# rpi-receiver.net
KiCad netlist of a schematic drawn in EAGLE
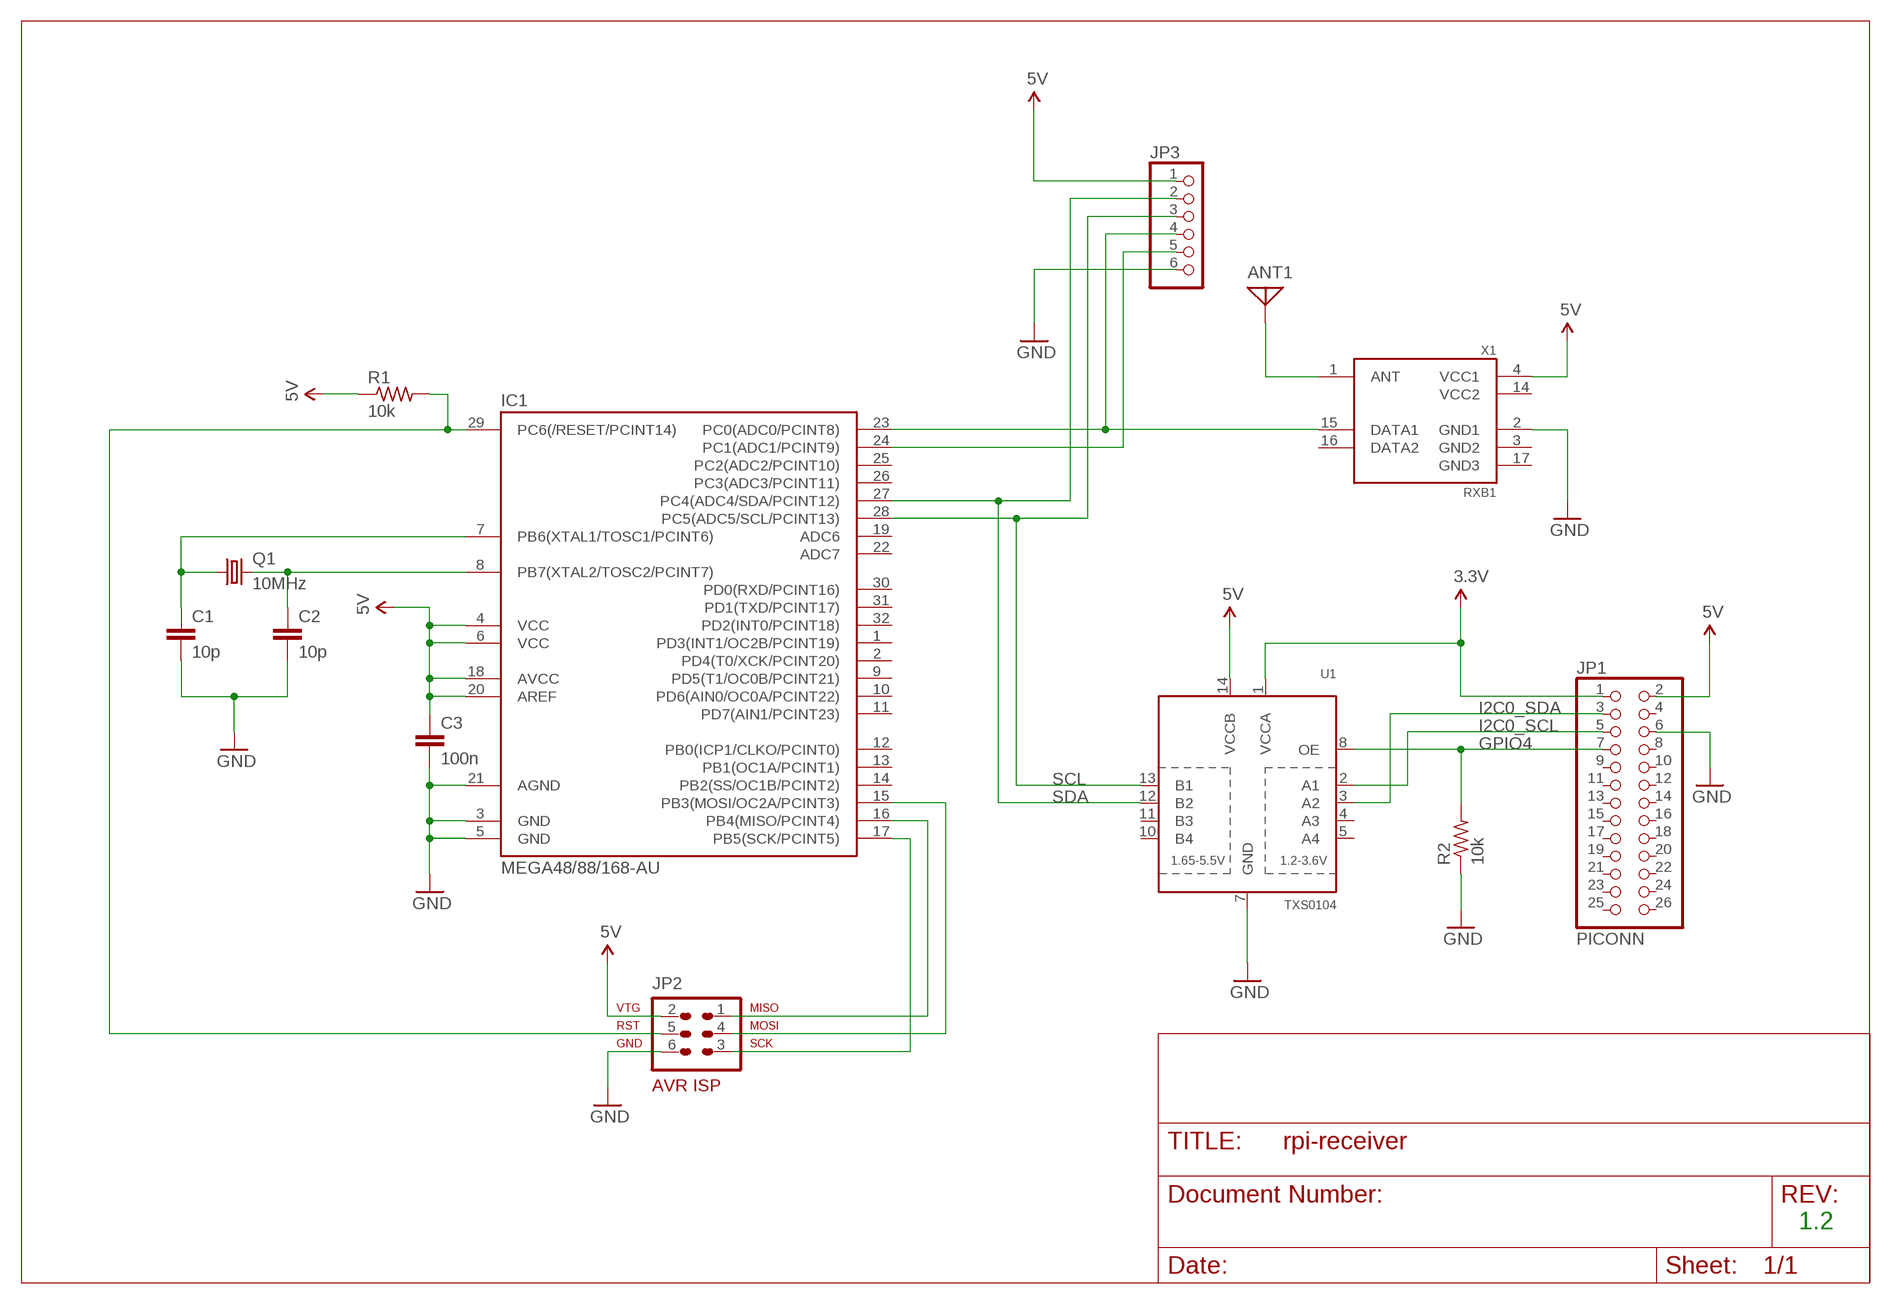
[diagram p0: schematic, sheet 1]

(export (version "E")
  (design (tool "Eeschema 10.0.6"))
  (components
    (comp (ref "ANT1")
      (value "ANTENNA")
      (footprint "eagle-import:PAD-01")
      (libsource (lib "eagle-import") (part "ANTENNA"))
    )
    (comp (ref "C1")
      (value "10p")
      (footprint "eagle-import:C0805")
      (libsource (lib "eagle-import") (part "C-EUC0805"))
    )
    (comp (ref "C2")
      (value "10p")
      (footprint "eagle-import:C0805")
      (libsource (lib "eagle-import") (part "C-EUC0805"))
    )
    (comp (ref "C3")
      (value "100n")
      (footprint "eagle-import:C0805")
      (libsource (lib "eagle-import") (part "C-EUC0805"))
    )
    (comp (ref "IC1")
      (value "MEGA48/88/168-AU")
      (footprint "eagle-import:TQFP32-08")
      (libsource (lib "eagle-import") (part "MEGA48/88/168-AU"))
    )
    (comp (ref "JP1")
      (value "PICONN")
      (footprint "eagle-import:2X13")
      (libsource (lib "eagle-import") (part "PINHD-2X13"))
    )
    (comp (ref "JP2")
      (value "AVR-ISP-6POL-HDR")
      (footprint "eagle-import:22-23-2061")
      (libsource (lib "eagle-import") (part "AVR-ISP-6POL-HDR"))
    )
    (comp (ref "JP3")
      (value "PINHD-1X6")
      (footprint "eagle-import:1X06")
      (libsource (lib "eagle-import") (part "PINHD-1X6"))
    )
    (comp (ref "Q1")
      (value "10MHz")
      (footprint "eagle-import:HC49UP")
      (libsource (lib "eagle-import") (part "CRYSTALHC49UP"))
    )
    (comp (ref "R1")
      (value "10k")
      (footprint "eagle-import:M0805")
      (libsource (lib "eagle-import") (part "R-US_M0805"))
    )
    (comp (ref "R2")
      (value "10k")
      (footprint "eagle-import:M0805")
      (libsource (lib "eagle-import") (part "R-US_M0805"))
    )
    (comp (ref "U1")
      (value "TXS0104")
      (footprint "eagle-import:TSSOP14")
      (libsource (lib "eagle-import") (part "TXB0104PWR"))
    )
    (comp (ref "X1")
      (value "RXB1")
      (footprint "eagle-import:RXB1")
      (libsource (lib "eagle-import") (part "RXB1"))
    )
  )
  (nets
    (net (code "1") (name "/GND2") (class "Default")
      (node (ref "X1") (pin "3") (pinfunction "GND2_3") (pintype "power_in"))
    )
    (net (code "2") (name "/GND3") (class "Default")
      (node (ref "X1") (pin "17") (pinfunction "GND3_17") (pintype "power_in"))
    )
    (net (code "3") (name "/GPIO4") (class "Default")
      (node (ref "JP1") (pin "7") (pinfunction "7_7") (pintype "passive"))
      (node (ref "R2") (pin "2") (pinfunction "2_2") (pintype "passive"))
      (node (ref "U1") (pin "8") (pinfunction "OE_8") (pintype "bidirectional"))
    )
    (net (code "4") (name "/I2C0_SCL") (class "Default")
      (node (ref "JP1") (pin "5") (pinfunction "5_5") (pintype "passive"))
      (node (ref "U1") (pin "2") (pinfunction "A1_2") (pintype "bidirectional"))
    )
    (net (code "5") (name "/I2C0_SDA") (class "Default")
      (node (ref "JP1") (pin "3") (pinfunction "3_3") (pintype "passive"))
      (node (ref "U1") (pin "3") (pinfunction "A2_3") (pintype "bidirectional"))
    )
    (net (code "6") (name "/SCL") (class "Default")
      (node (ref "IC1") (pin "28") (pinfunction "PC5(ADC5/SCL/PCINT13)_28") (pintype "bidirectional"))
      (node (ref "JP3") (pin "3") (pinfunction "3_3") (pintype "passive"))
      (node (ref "U1") (pin "13") (pinfunction "B1_13") (pintype "bidirectional"))
    )
    (net (code "7") (name "/SDA") (class "Default")
      (node (ref "IC1") (pin "27") (pinfunction "PC4(ADC4/SDA/PCINT12)_27") (pintype "bidirectional"))
      (node (ref "JP3") (pin "2") (pinfunction "2_2") (pintype "passive"))
      (node (ref "U1") (pin "12") (pinfunction "B2_12") (pintype "bidirectional"))
    )
    (net (code "8") (name "/VCC2") (class "Default")
      (node (ref "X1") (pin "14") (pinfunction "VCC2_14") (pintype "power_in"))
    )
    (net (code "9") (name "3.3V") (class "Default")
      (node (ref "JP1") (pin "1") (pinfunction "1_1") (pintype "passive"))
      (node (ref "U1") (pin "1") (pinfunction "VCCA_1") (pintype "bidirectional"))
    )
    (net (code "10") (name "5V") (class "Default")
      (node (ref "C3") (pin "1") (pinfunction "1_1") (pintype "passive"))
      (node (ref "IC1") (pin "18") (pinfunction "AVCC_18") (pintype "passive"))
      (node (ref "IC1") (pin "20") (pinfunction "AREF_20") (pintype "passive"))
      (node (ref "IC1") (pin "4") (pinfunction "VCC_4") (pintype "power_in"))
      (node (ref "IC1") (pin "6") (pinfunction "VCC_6") (pintype "power_in"))
      (node (ref "JP1") (pin "2") (pinfunction "2_2") (pintype "passive"))
      (node (ref "JP2") (pin "2") (pinfunction "2_2") (pintype "passive"))
      (node (ref "JP3") (pin "1") (pinfunction "1_1") (pintype "passive"))
      (node (ref "R1") (pin "1") (pinfunction "1_1") (pintype "passive"))
      (node (ref "U1") (pin "14") (pinfunction "VCCB_14") (pintype "bidirectional"))
      (node (ref "X1") (pin "4") (pinfunction "VCC1_4") (pintype "power_in"))
    )
    (net (code "11") (name "GND") (class "Default")
      (node (ref "C1") (pin "2") (pinfunction "2_2") (pintype "passive"))
      (node (ref "C2") (pin "2") (pinfunction "2_2") (pintype "passive"))
      (node (ref "C3") (pin "2") (pinfunction "2_2") (pintype "passive"))
      (node (ref "IC1") (pin "21") (pinfunction "AGND_21") (pintype "power_in"))
      (node (ref "IC1") (pin "3") (pinfunction "GND_3") (pintype "power_in"))
      (node (ref "IC1") (pin "5") (pinfunction "GND_5") (pintype "power_in"))
      (node (ref "JP1") (pin "6") (pinfunction "6_6") (pintype "passive"))
      (node (ref "JP2") (pin "6") (pinfunction "6_6") (pintype "passive"))
      (node (ref "JP3") (pin "6") (pinfunction "6_6") (pintype "passive"))
      (node (ref "R2") (pin "1") (pinfunction "1_1") (pintype "passive"))
      (node (ref "U1") (pin "7") (pinfunction "GND_7") (pintype "bidirectional"))
      (node (ref "X1") (pin "2") (pinfunction "GND1_2") (pintype "power_in"))
    )
    (net (code "12") (name "Net-(IC1-PB3(MOSI{slash}OC2A{slash}PCINT3))") (class "Default")
      (node (ref "IC1") (pin "15") (pinfunction "PB3(MOSI/OC2A/PCINT3)_15") (pintype "bidirectional"))
      (node (ref "JP2") (pin "4") (pinfunction "4_4") (pintype "passive"))
    )
    (net (code "13") (name "Net-(IC1-PB4(MISO{slash}PCINT4))") (class "Default")
      (node (ref "IC1") (pin "16") (pinfunction "PB4(MISO/PCINT4)_16") (pintype "bidirectional"))
      (node (ref "JP2") (pin "1") (pinfunction "1_1") (pintype "passive"))
    )
    (net (code "14") (name "Net-(IC1-PB5(SCK{slash}PCINT5))") (class "Default")
      (node (ref "IC1") (pin "17") (pinfunction "PB5(SCK/PCINT5)_17") (pintype "bidirectional"))
      (node (ref "JP2") (pin "3") (pinfunction "3_3") (pintype "passive"))
    )
    (net (code "15") (name "Net-(IC1-PB6(XTAL1{slash}TOSC1{slash}PCINT6))") (class "Default")
      (node (ref "C1") (pin "1") (pinfunction "1_1") (pintype "passive"))
      (node (ref "IC1") (pin "7") (pinfunction "PB6(XTAL1/TOSC1/PCINT6)_7") (pintype "bidirectional"))
      (node (ref "Q1") (pin "1") (pinfunction "1_1") (pintype "passive"))
    )
    (net (code "16") (name "Net-(IC1-PB7(XTAL2{slash}TOSC2{slash}PCINT7))") (class "Default")
      (node (ref "C2") (pin "1") (pinfunction "1_1") (pintype "passive"))
      (node (ref "IC1") (pin "8") (pinfunction "PB7(XTAL2/TOSC2/PCINT7)_8") (pintype "bidirectional"))
      (node (ref "Q1") (pin "2") (pinfunction "2_2") (pintype "passive"))
    )
    (net (code "17") (name "Net-(IC1-PC0(ADC0{slash}PCINT8))") (class "Default")
      (node (ref "IC1") (pin "23") (pinfunction "PC0(ADC0/PCINT8)_23") (pintype "bidirectional"))
      (node (ref "JP3") (pin "4") (pinfunction "4_4") (pintype "passive"))
      (node (ref "X1") (pin "15") (pinfunction "DATA1_15") (pintype "output"))
    )
    (net (code "18") (name "Net-(IC1-PC1(ADC1{slash}PCINT9))") (class "Default")
      (node (ref "IC1") (pin "24") (pinfunction "PC1(ADC1/PCINT9)_24") (pintype "bidirectional"))
      (node (ref "JP3") (pin "5") (pinfunction "5_5") (pintype "passive"))
    )
    (net (code "19") (name "Net-(IC1-PC6({slash}RESET{slash}PCINT14))") (class "Default")
      (node (ref "IC1") (pin "29") (pinfunction "PC6(/RESET/PCINT14)_29") (pintype "bidirectional"))
      (node (ref "JP2") (pin "5") (pinfunction "5_5") (pintype "passive"))
      (node (ref "R1") (pin "2") (pinfunction "2_2") (pintype "passive"))
    )
    (net (code "20") (name "Net-(X1-ANT)") (class "Default")
      (node (ref "ANT1") (pin "1") (pinfunction "1_1") (pintype "output"))
      (node (ref "X1") (pin "1") (pinfunction "ANT_1") (pintype "bidirectional"))
    )
    (net (code "21") (name "unconnected-(IC1-ADC6-Pad19)") (class "Default")
      (node (ref "IC1") (pin "19") (pinfunction "ADC6_19") (pintype "passive"))
    )
    (net (code "22") (name "unconnected-(IC1-ADC7-Pad22)") (class "Default")
      (node (ref "IC1") (pin "22") (pinfunction "ADC7_22") (pintype "passive"))
    )
    (net (code "23") (name "unconnected-(IC1-PB0(ICP1{slash}CLKO{slash}PCINT0)-Pad12)") (class "Default")
      (node (ref "IC1") (pin "12") (pinfunction "PB0(ICP1/CLKO/PCINT0)_12") (pintype "bidirectional"))
    )
    (net (code "24") (name "unconnected-(IC1-PB1(OC1A{slash}PCINT1)-Pad13)") (class "Default")
      (node (ref "IC1") (pin "13") (pinfunction "PB1(OC1A/PCINT1)_13") (pintype "bidirectional"))
    )
    (net (code "25") (name "unconnected-(IC1-PB2(SS{slash}OC1B{slash}PCINT2)-Pad14)") (class "Default")
      (node (ref "IC1") (pin "14") (pinfunction "PB2(SS/OC1B/PCINT2)_14") (pintype "bidirectional"))
    )
    (net (code "26") (name "unconnected-(IC1-PC2(ADC2{slash}PCINT10)-Pad25)") (class "Default")
      (node (ref "IC1") (pin "25") (pinfunction "PC2(ADC2/PCINT10)_25") (pintype "bidirectional"))
    )
    (net (code "27") (name "unconnected-(IC1-PC3(ADC3{slash}PCINT11)-Pad26)") (class "Default")
      (node (ref "IC1") (pin "26") (pinfunction "PC3(ADC3/PCINT11)_26") (pintype "bidirectional"))
    )
    (net (code "28") (name "unconnected-(IC1-PD0(RXD{slash}PCINT16)-Pad30)") (class "Default")
      (node (ref "IC1") (pin "30") (pinfunction "PD0(RXD/PCINT16)_30") (pintype "bidirectional"))
    )
    (net (code "29") (name "unconnected-(IC1-PD1(TXD{slash}PCINT17)-Pad31)") (class "Default")
      (node (ref "IC1") (pin "31") (pinfunction "PD1(TXD/PCINT17)_31") (pintype "bidirectional"))
    )
    (net (code "30") (name "unconnected-(IC1-PD2(INT0{slash}PCINT18)-Pad32)") (class "Default")
      (node (ref "IC1") (pin "32") (pinfunction "PD2(INT0/PCINT18)_32") (pintype "bidirectional"))
    )
    (net (code "31") (name "unconnected-(IC1-PD3(INT1{slash}OC2B{slash}PCINT19)-Pad1)") (class "Default")
      (node (ref "IC1") (pin "1") (pinfunction "PD3(INT1/OC2B/PCINT19)_1") (pintype "bidirectional"))
    )
    (net (code "32") (name "unconnected-(IC1-PD4(T0{slash}XCK{slash}PCINT20)-Pad2)") (class "Default")
      (node (ref "IC1") (pin "2") (pinfunction "PD4(T0/XCK/PCINT20)_2") (pintype "bidirectional"))
    )
    (net (code "33") (name "unconnected-(IC1-PD5(T1{slash}OC0B{slash}PCINT21)-Pad9)") (class "Default")
      (node (ref "IC1") (pin "9") (pinfunction "PD5(T1/OC0B/PCINT21)_9") (pintype "bidirectional"))
    )
    (net (code "34") (name "unconnected-(IC1-PD6(AIN0{slash}OC0A{slash}PCINT22)-Pad10)") (class "Default")
      (node (ref "IC1") (pin "10") (pinfunction "PD6(AIN0/OC0A/PCINT22)_10") (pintype "bidirectional"))
    )
    (net (code "35") (name "unconnected-(IC1-PD7(AIN1{slash}PCINT23)-Pad11)") (class "Default")
      (node (ref "IC1") (pin "11") (pinfunction "PD7(AIN1/PCINT23)_11") (pintype "bidirectional"))
    )
    (net (code "36") (name "unconnected-(JP1-Pad4)") (class "Default")
      (node (ref "JP1") (pin "4") (pinfunction "4_4") (pintype "passive"))
    )
    (net (code "37") (name "unconnected-(JP1-Pad8)") (class "Default")
      (node (ref "JP1") (pin "8") (pinfunction "8_8") (pintype "passive"))
    )
    (net (code "38") (name "unconnected-(JP1-Pad9)") (class "Default")
      (node (ref "JP1") (pin "9") (pinfunction "9_9") (pintype "passive"))
    )
    (net (code "39") (name "unconnected-(JP1-Pad10)") (class "Default")
      (node (ref "JP1") (pin "10") (pinfunction "10_10") (pintype "passive"))
    )
    (net (code "40") (name "unconnected-(JP1-Pad11)") (class "Default")
      (node (ref "JP1") (pin "11") (pinfunction "11_11") (pintype "passive"))
    )
    (net (code "41") (name "unconnected-(JP1-Pad12)") (class "Default")
      (node (ref "JP1") (pin "12") (pinfunction "12_12") (pintype "passive"))
    )
    (net (code "42") (name "unconnected-(JP1-Pad13)") (class "Default")
      (node (ref "JP1") (pin "13") (pinfunction "13_13") (pintype "passive"))
    )
    (net (code "43") (name "unconnected-(JP1-Pad14)") (class "Default")
      (node (ref "JP1") (pin "14") (pinfunction "14_14") (pintype "passive"))
    )
    (net (code "44") (name "unconnected-(JP1-Pad15)") (class "Default")
      (node (ref "JP1") (pin "15") (pinfunction "15_15") (pintype "passive"))
    )
    (net (code "45") (name "unconnected-(JP1-Pad16)") (class "Default")
      (node (ref "JP1") (pin "16") (pinfunction "16_16") (pintype "passive"))
    )
    (net (code "46") (name "unconnected-(JP1-Pad17)") (class "Default")
      (node (ref "JP1") (pin "17") (pinfunction "17_17") (pintype "passive"))
    )
    (net (code "47") (name "unconnected-(JP1-Pad18)") (class "Default")
      (node (ref "JP1") (pin "18") (pinfunction "18_18") (pintype "passive"))
    )
    (net (code "48") (name "unconnected-(JP1-Pad19)") (class "Default")
      (node (ref "JP1") (pin "19") (pinfunction "19_19") (pintype "passive"))
    )
    (net (code "49") (name "unconnected-(JP1-Pad20)") (class "Default")
      (node (ref "JP1") (pin "20") (pinfunction "20_20") (pintype "passive"))
    )
    (net (code "50") (name "unconnected-(JP1-Pad21)") (class "Default")
      (node (ref "JP1") (pin "21") (pinfunction "21_21") (pintype "passive"))
    )
    (net (code "51") (name "unconnected-(JP1-Pad22)") (class "Default")
      (node (ref "JP1") (pin "22") (pinfunction "22_22") (pintype "passive"))
    )
    (net (code "52") (name "unconnected-(JP1-Pad23)") (class "Default")
      (node (ref "JP1") (pin "23") (pinfunction "23_23") (pintype "passive"))
    )
    (net (code "53") (name "unconnected-(JP1-Pad24)") (class "Default")
      (node (ref "JP1") (pin "24") (pinfunction "24_24") (pintype "passive"))
    )
    (net (code "54") (name "unconnected-(JP1-Pad25)") (class "Default")
      (node (ref "JP1") (pin "25") (pinfunction "25_25") (pintype "passive"))
    )
    (net (code "55") (name "unconnected-(JP1-Pad26)") (class "Default")
      (node (ref "JP1") (pin "26") (pinfunction "26_26") (pintype "passive"))
    )
    (net (code "56") (name "unconnected-(U1-A3-Pad4)") (class "Default")
      (node (ref "U1") (pin "4") (pinfunction "A3_4") (pintype "bidirectional"))
    )
    (net (code "57") (name "unconnected-(U1-A4-Pad5)") (class "Default")
      (node (ref "U1") (pin "5") (pinfunction "A4_5") (pintype "bidirectional"))
    )
    (net (code "58") (name "unconnected-(U1-B3-Pad11)") (class "Default")
      (node (ref "U1") (pin "11") (pinfunction "B3_11") (pintype "bidirectional"))
    )
    (net (code "59") (name "unconnected-(U1-B4-Pad10)") (class "Default")
      (node (ref "U1") (pin "10") (pinfunction "B4_10") (pintype "bidirectional"))
    )
    (net (code "60") (name "unconnected-(X1-DATA2-Pad16)") (class "Default")
      (node (ref "X1") (pin "16") (pinfunction "DATA2_16") (pintype "output"))
    )
  )
)
